# SOT-23_Breakout.net
KiCad netlist of a schematic drawn in EAGLE
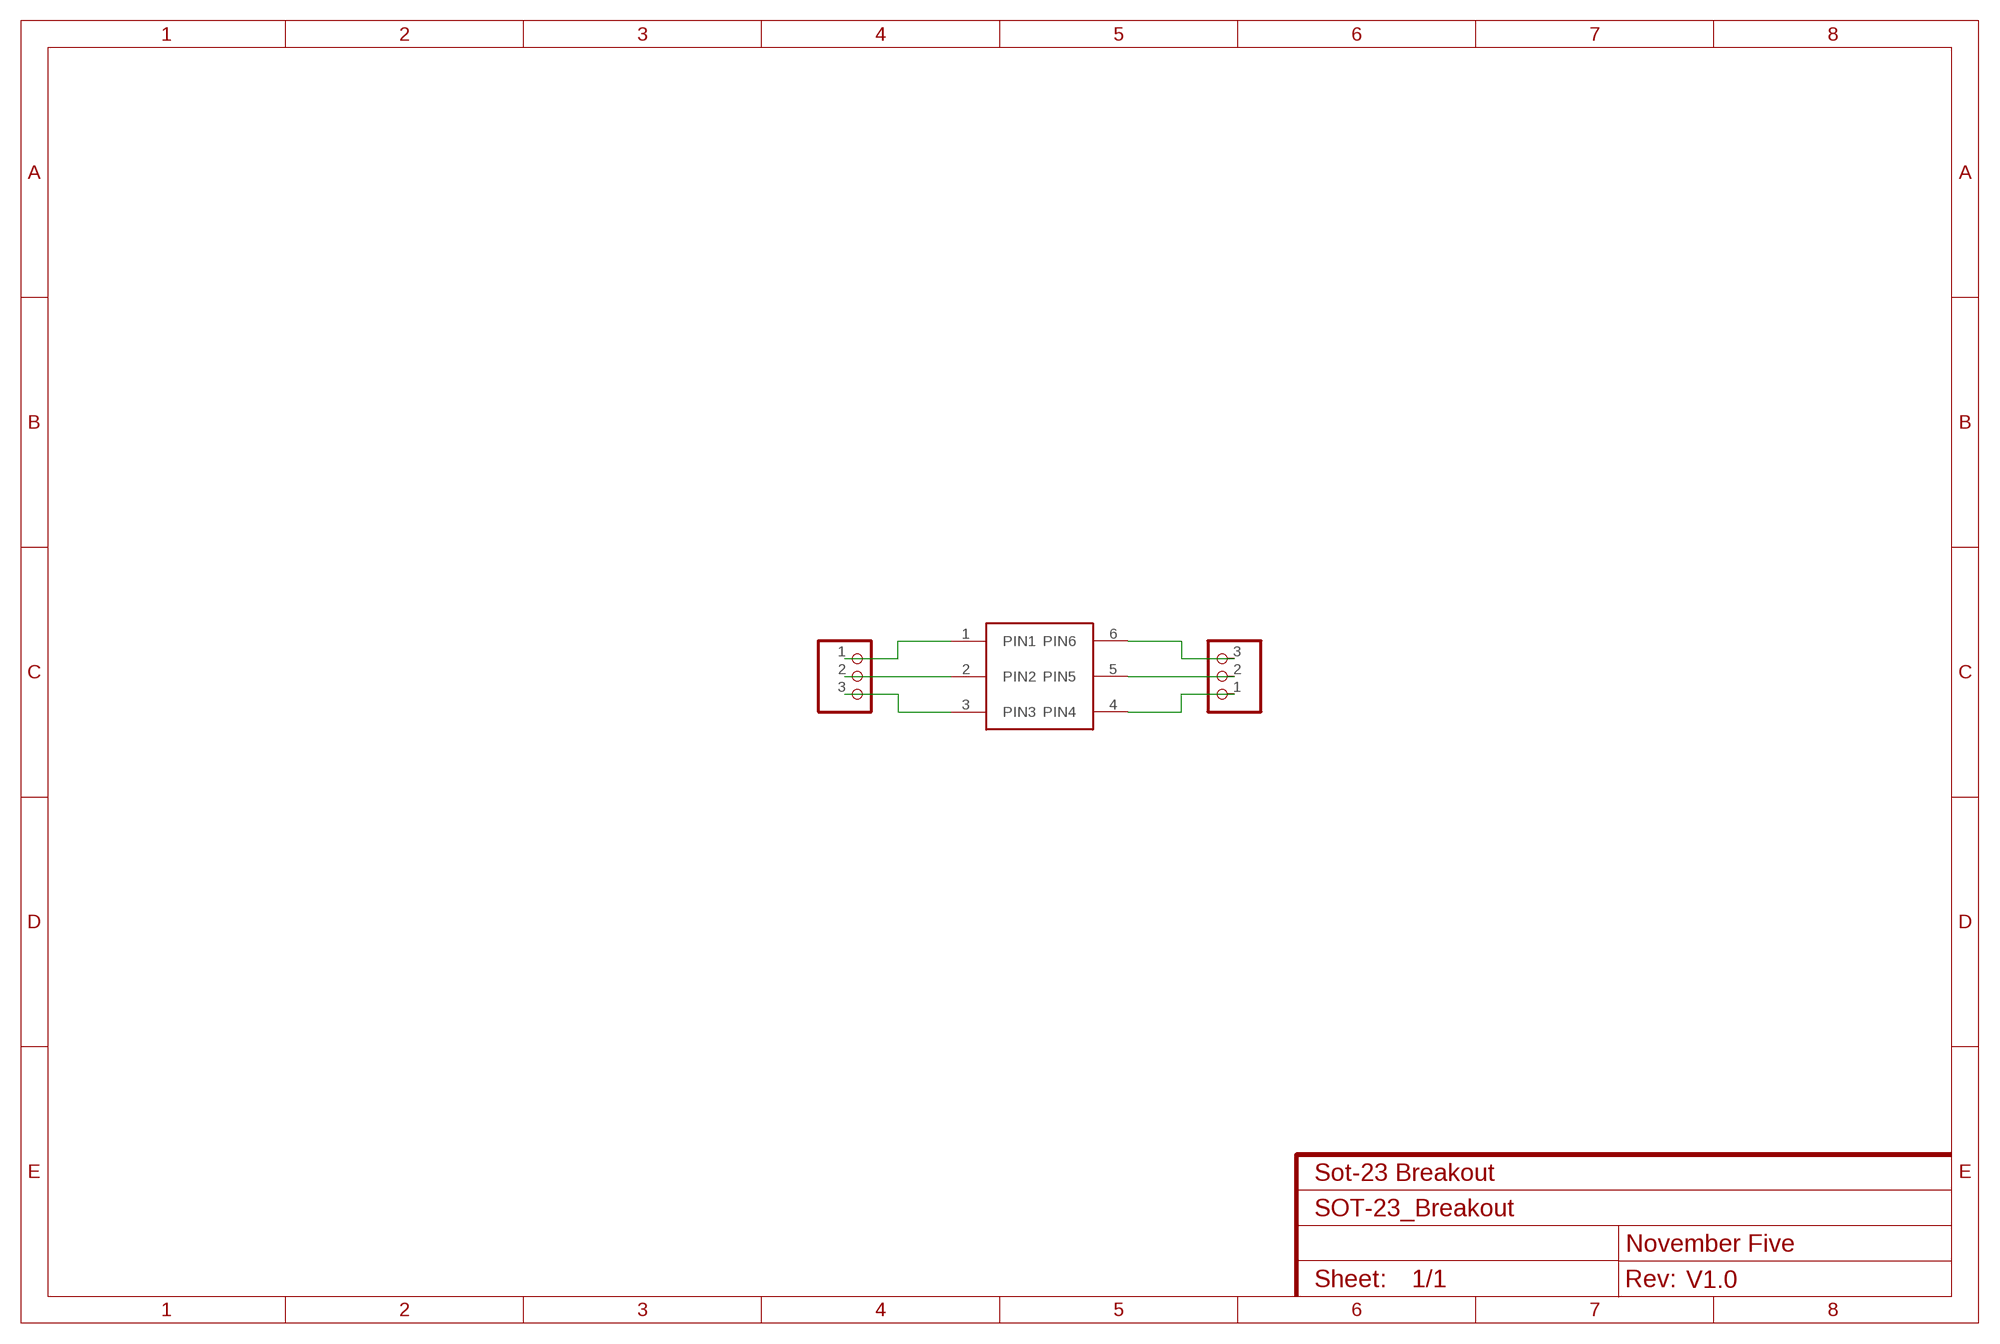
[diagram p0: schematic, sheet 1]

(export (version "E")
  (design (tool "Eeschema 10.0.6"))
  (components
    (comp (ref ".")
      (value "SOT-23-6")
      (footprint "eagle-import:SOT-23-6")
      (libsource (lib "eagle-import") (part "SOT-23-6"))
    )
    (comp (ref "JP1")
      (value "PINHD-1X3")
      (footprint "eagle-import:1X03")
      (libsource (lib "eagle-import") (part "PINHD-1X3"))
    )
    (comp (ref "JP2")
      (value "PINHD-1X3")
      (footprint "eagle-import:1X03")
      (libsource (lib "eagle-import") (part "PINHD-1X3"))
    )
  )
  (nets
    (net (code "1") (name "Net-(.-PIN1)") (class "Default")
      (node (ref ".") (pin "1") (pinfunction "PIN1_1") (pintype "bidirectional"))
      (node (ref "JP1") (pin "1") (pinfunction "1_1") (pintype "passive"))
    )
    (net (code "2") (name "Net-(.-PIN2)") (class "Default")
      (node (ref ".") (pin "2") (pinfunction "PIN2_2") (pintype "bidirectional"))
      (node (ref "JP1") (pin "2") (pinfunction "2_2") (pintype "passive"))
    )
    (net (code "3") (name "Net-(.-PIN3)") (class "Default")
      (node (ref ".") (pin "3") (pinfunction "PIN3_3") (pintype "bidirectional"))
      (node (ref "JP1") (pin "3") (pinfunction "3_3") (pintype "passive"))
    )
    (net (code "4") (name "Net-(.-PIN4)") (class "Default")
      (node (ref ".") (pin "4") (pinfunction "PIN4_4") (pintype "bidirectional"))
      (node (ref "JP2") (pin "1") (pinfunction "1_1") (pintype "passive"))
    )
    (net (code "5") (name "Net-(.-PIN5)") (class "Default")
      (node (ref ".") (pin "5") (pinfunction "PIN5_5") (pintype "bidirectional"))
      (node (ref "JP2") (pin "2") (pinfunction "2_2") (pintype "passive"))
    )
    (net (code "6") (name "Net-(.-PIN6)") (class "Default")
      (node (ref ".") (pin "6") (pinfunction "PIN6_6") (pintype "bidirectional"))
      (node (ref "JP2") (pin "3") (pinfunction "3_3") (pintype "passive"))
    )
  )
)
